# Digital_Input_Reader_and_Protection_Circ.net
KiCad netlist of a schematic drawn in EAGLE
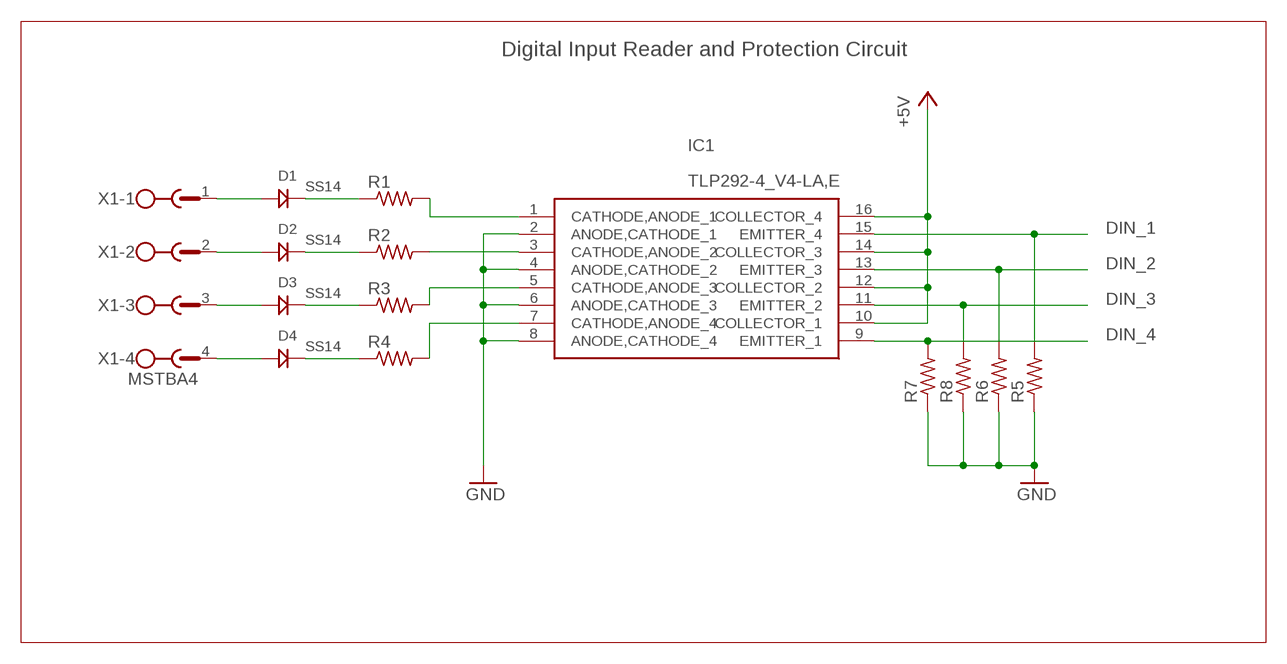
[diagram p0: schematic, sheet 1]

(export (version "E")
  (design (tool "Eeschema 10.0.6"))
  (components
    (comp (ref "D1")
      (value "SS14")
      (footprint "eagle-import:DO214")
      (fields (field (name "MF") "ON Semiconductor"))
      (libsource (lib "eagle-import") (part "SS14"))
    )
    (comp (ref "D2")
      (value "SS14")
      (footprint "eagle-import:DO214")
      (fields (field (name "MF") "ON Semiconductor"))
      (libsource (lib "eagle-import") (part "SS14"))
    )
    (comp (ref "D3")
      (value "SS14")
      (footprint "eagle-import:DO214")
      (fields (field (name "MF") "ON Semiconductor"))
      (libsource (lib "eagle-import") (part "SS14"))
    )
    (comp (ref "D4")
      (value "SS14")
      (footprint "eagle-import:DO214")
      (fields (field (name "MF") "ON Semiconductor"))
      (libsource (lib "eagle-import") (part "SS14"))
    )
    (comp (ref "IC1")
      (value "TLP292-4_V4-LA,E")
      (footprint "eagle-import:SOIC127P700X230-16N")
      (fields
        (field (name "ARROW_PART_NUMBER") "TLP292-4(V4-LA,E")
        (field (name "MOUSER_PART_NUMBER") "757-TLP292-4V4-LAE")
      )
      (libsource (lib "eagle-import") (part "TLP292-4_V4-LA,E"))
    )
    (comp (ref "R1")
      (value "R-US_R0805")
      (footprint "eagle-import:R0805")
      (libsource (lib "eagle-import") (part "R-US_R0805"))
    )
    (comp (ref "R2")
      (value "R-US_R0805")
      (footprint "eagle-import:R0805")
      (libsource (lib "eagle-import") (part "R-US_R0805"))
    )
    (comp (ref "R3")
      (value "R-US_R0805")
      (footprint "eagle-import:R0805")
      (libsource (lib "eagle-import") (part "R-US_R0805"))
    )
    (comp (ref "R4")
      (value "R-US_R0805")
      (footprint "eagle-import:R0805")
      (libsource (lib "eagle-import") (part "R-US_R0805"))
    )
    (comp (ref "R5")
      (value "R-US_R0805")
      (footprint "eagle-import:R0805")
      (libsource (lib "eagle-import") (part "R-US_R0805"))
    )
    (comp (ref "R6")
      (value "R-US_R0805")
      (footprint "eagle-import:R0805")
      (libsource (lib "eagle-import") (part "R-US_R0805"))
    )
    (comp (ref "R7")
      (value "R-US_R0805")
      (footprint "eagle-import:R0805")
      (libsource (lib "eagle-import") (part "R-US_R0805"))
    )
    (comp (ref "R8")
      (value "R-US_R0805")
      (footprint "eagle-import:R0805")
      (libsource (lib "eagle-import") (part "R-US_R0805"))
    )
    (comp (ref "X1")
      (value "MSTBA4")
      (footprint "eagle-import:MSTBA4")
      (fields (field (name "MF") "FARNELL") (field (name "MPN") "1757268"))
      (libsource (lib "eagle-import") (part "MSTBA4"))
    )
  )
  (nets
    (net (code "1") (name "+5V") (class "Default")
      (node (ref "IC1") (pin "10") (pinfunction "COLLECTOR_1_10") (pintype "bidirectional"))
      (node (ref "IC1") (pin "12") (pinfunction "COLLECTOR_2_12") (pintype "bidirectional"))
      (node (ref "IC1") (pin "14") (pinfunction "COLLECTOR_3_14") (pintype "bidirectional"))
      (node (ref "IC1") (pin "16") (pinfunction "COLLECTOR_4_16") (pintype "bidirectional"))
    )
    (net (code "2") (name "/DIN_1") (class "Default")
      (node (ref "IC1") (pin "15") (pinfunction "EMITTER_4_15") (pintype "bidirectional"))
      (node (ref "R5") (pin "2") (pinfunction "2_2") (pintype "passive"))
    )
    (net (code "3") (name "/DIN_2") (class "Default")
      (node (ref "IC1") (pin "13") (pinfunction "EMITTER_3_13") (pintype "bidirectional"))
      (node (ref "R6") (pin "2") (pinfunction "2_2") (pintype "passive"))
    )
    (net (code "4") (name "/DIN_3") (class "Default")
      (node (ref "IC1") (pin "11") (pinfunction "EMITTER_2_11") (pintype "bidirectional"))
      (node (ref "R8") (pin "2") (pinfunction "2_2") (pintype "passive"))
    )
    (net (code "5") (name "/DIN_4") (class "Default")
      (node (ref "IC1") (pin "9") (pinfunction "EMITTER_1_9") (pintype "bidirectional"))
      (node (ref "R7") (pin "2") (pinfunction "2_2") (pintype "passive"))
    )
    (net (code "6") (name "GND") (class "Default")
      (node (ref "IC1") (pin "2") (pinfunction "ANODE,CATHODE_1_2") (pintype "bidirectional"))
      (node (ref "IC1") (pin "4") (pinfunction "ANODE,CATHODE_2_4") (pintype "bidirectional"))
      (node (ref "IC1") (pin "6") (pinfunction "ANODE,CATHODE_3_6") (pintype "bidirectional"))
      (node (ref "IC1") (pin "8") (pinfunction "ANODE,CATHODE_4_8") (pintype "bidirectional"))
      (node (ref "R5") (pin "1") (pinfunction "1_1") (pintype "passive"))
      (node (ref "R6") (pin "1") (pinfunction "1_1") (pintype "passive"))
      (node (ref "R7") (pin "1") (pinfunction "1_1") (pintype "passive"))
      (node (ref "R8") (pin "1") (pinfunction "1_1") (pintype "passive"))
    )
    (net (code "7") (name "Net-(D1-KATHODE)") (class "Default")
      (node (ref "D1") (pin "CATHODE") (pinfunction "KATHODE_CATHODE") (pintype "bidirectional"))
      (node (ref "R1") (pin "1") (pinfunction "1_1") (pintype "passive"))
    )
    (net (code "8") (name "Net-(D1-PadANODE)") (class "Default")
      (node (ref "D1") (pin "ANODE") (pinfunction "ANODE_ANODE") (pintype "bidirectional"))
      (node (ref "X1") (pin "1") (pinfunction "1_1") (pintype "passive"))
    )
    (net (code "9") (name "Net-(D2-KATHODE)") (class "Default")
      (node (ref "D2") (pin "CATHODE") (pinfunction "KATHODE_CATHODE") (pintype "bidirectional"))
      (node (ref "R2") (pin "1") (pinfunction "1_1") (pintype "passive"))
    )
    (net (code "10") (name "Net-(D3-KATHODE)") (class "Default")
      (node (ref "D3") (pin "CATHODE") (pinfunction "KATHODE_CATHODE") (pintype "bidirectional"))
      (node (ref "R3") (pin "1") (pinfunction "1_1") (pintype "passive"))
    )
    (net (code "11") (name "Net-(D4-KATHODE)") (class "Default")
      (node (ref "D4") (pin "CATHODE") (pinfunction "KATHODE_CATHODE") (pintype "bidirectional"))
      (node (ref "R4") (pin "1") (pinfunction "1_1") (pintype "passive"))
    )
    (net (code "12") (name "Net-(IC1-CATHODE,ANODE_1)") (class "Default")
      (node (ref "IC1") (pin "1") (pinfunction "CATHODE,ANODE_1_1") (pintype "bidirectional"))
      (node (ref "R1") (pin "2") (pinfunction "2_2") (pintype "passive"))
    )
    (net (code "13") (name "Net-(IC1-CATHODE,ANODE_2)") (class "Default")
      (node (ref "IC1") (pin "3") (pinfunction "CATHODE,ANODE_2_3") (pintype "bidirectional"))
      (node (ref "R2") (pin "2") (pinfunction "2_2") (pintype "passive"))
    )
    (net (code "14") (name "Net-(IC1-CATHODE,ANODE_3)") (class "Default")
      (node (ref "IC1") (pin "5") (pinfunction "CATHODE,ANODE_3_5") (pintype "bidirectional"))
      (node (ref "R3") (pin "2") (pinfunction "2_2") (pintype "passive"))
    )
    (net (code "15") (name "Net-(IC1-CATHODE,ANODE_4)") (class "Default")
      (node (ref "IC1") (pin "7") (pinfunction "CATHODE,ANODE_4_7") (pintype "bidirectional"))
      (node (ref "R4") (pin "2") (pinfunction "2_2") (pintype "passive"))
    )
    (net (code "16") (name "Net-(X1B-1)") (class "Default")
      (node (ref "D2") (pin "ANODE") (pinfunction "ANODE_ANODE") (pintype "bidirectional"))
      (node (ref "X1") (pin "2") (pinfunction "1_2") (pintype "passive"))
    )
    (net (code "17") (name "Net-(X1C-1)") (class "Default")
      (node (ref "D3") (pin "ANODE") (pinfunction "ANODE_ANODE") (pintype "bidirectional"))
      (node (ref "X1") (pin "3") (pinfunction "1_3") (pintype "passive"))
    )
    (net (code "18") (name "Net-(X1D-1)") (class "Default")
      (node (ref "D4") (pin "ANODE") (pinfunction "ANODE_ANODE") (pintype "bidirectional"))
      (node (ref "X1") (pin "4") (pinfunction "1_4") (pintype "passive"))
    )
  )
)
